# uMultimeter_ExpDev_Sch.net
KiCad netlist of a schematic drawn in Altium Designer
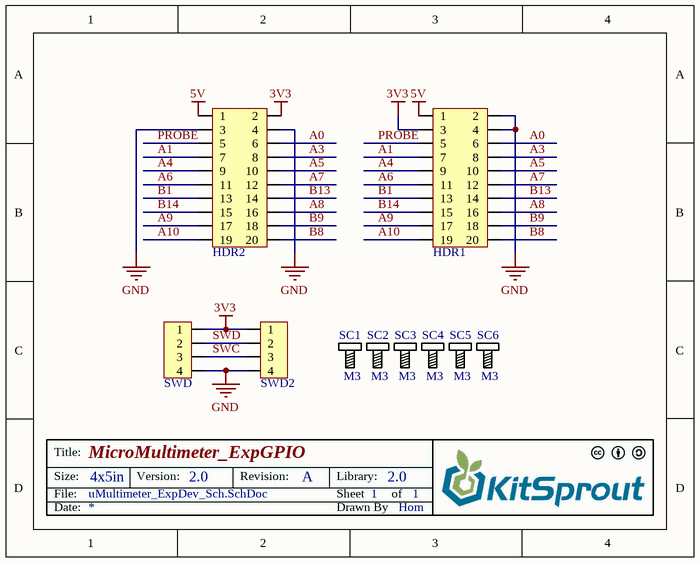
[diagram p0: uMultimeter_ExpDev_Sch.SchDoc]

(export (version "E")
  (design (tool "Eeschema 10.0.6"))
  (components
    (comp (ref "HDR1")
      (value "HDR2x10_2.54")
      (footprint "PCB_ConnectorHDR:HDR2X10_2.54_90")
      (description "Header")
      (libsource (lib "SCH_ConnectorHDR") (part "HDR2x10_2.54"))
    )
    (comp (ref "HDR2")
      (value "HDR2x10_2.54")
      (footprint "PCB_ConnectorHDR:HDR2X10_2.54_180")
      (description "Header")
      (libsource (lib "SCH_ConnectorHDR") (part "HDR2x10_2.54"))
    )
    (comp (ref "SC1")
      (value "M3")
      (footprint "PCB_Mechanical:SCRREW_M3")
      (description "Screw")
      (libsource (lib "SCH_Mechanical") (part "Screw_M3"))
    )
    (comp (ref "SC2")
      (value "M3")
      (footprint "PCB_Mechanical:SCRREW_M3")
      (description "Screw")
      (libsource (lib "SCH_Mechanical") (part "Screw_M3"))
    )
    (comp (ref "SC3")
      (value "M3")
      (footprint "PCB_Mechanical:SCRREW_M3")
      (description "Screw")
      (libsource (lib "SCH_Mechanical") (part "Screw_M3"))
    )
    (comp (ref "SC4")
      (value "M3")
      (footprint "PCB_Mechanical:SCRREW_M3")
      (description "Screw")
      (libsource (lib "SCH_Mechanical") (part "Screw_M3"))
    )
    (comp (ref "SC5")
      (value "M3")
      (footprint "PCB_Mechanical:SCRREW_M3")
      (description "Screw")
      (libsource (lib "SCH_Mechanical") (part "Screw_M3"))
    )
    (comp (ref "SC6")
      (value "M3")
      (footprint "PCB_Mechanical:SCRREW_M3")
      (description "Screw")
      (libsource (lib "SCH_Mechanical") (part "Screw_M3"))
    )
    (comp (ref "SWD")
      (value "HDR1x4_1.27T")
      (footprint "PCB_ConnectorHDR:HDR1X4_1.27_180")
      (description "Header")
      (libsource (lib "SCH_ConnectorHDR") (part "HDR1x4_1.27T"))
    )
    (comp (ref "SWD2")
      (value "HDR1x4_2.54")
      (footprint "PCB_ConnectorHDR:HDR1X4_2.54_90F")
      (description "Header")
      (libsource (lib "SCH_ConnectorHDR") (part "HDR1x4_2.54"))
    )
  )
  (nets
    (net (code "1") (name "/A0") (class "Default")
      (node (ref "HDR1") (pin "6") (pinfunction "6_6") (pintype "passive"))
      (node (ref "HDR2") (pin "6") (pinfunction "6_6") (pintype "passive"))
    )
    (net (code "2") (name "/A1") (class "Default")
      (node (ref "HDR1") (pin "7") (pinfunction "7_7") (pintype "passive"))
      (node (ref "HDR2") (pin "7") (pinfunction "7_7") (pintype "passive"))
    )
    (net (code "3") (name "/A3") (class "Default")
      (node (ref "HDR1") (pin "8") (pinfunction "8_8") (pintype "passive"))
      (node (ref "HDR2") (pin "8") (pinfunction "8_8") (pintype "passive"))
    )
    (net (code "4") (name "/A4") (class "Default")
      (node (ref "HDR1") (pin "9") (pinfunction "9_9") (pintype "passive"))
      (node (ref "HDR2") (pin "9") (pinfunction "9_9") (pintype "passive"))
    )
    (net (code "5") (name "/A5") (class "Default")
      (node (ref "HDR1") (pin "10") (pinfunction "10_10") (pintype "passive"))
      (node (ref "HDR2") (pin "10") (pinfunction "10_10") (pintype "passive"))
    )
    (net (code "6") (name "/A6") (class "Default")
      (node (ref "HDR1") (pin "11") (pinfunction "11_11") (pintype "passive"))
      (node (ref "HDR2") (pin "11") (pinfunction "11_11") (pintype "passive"))
    )
    (net (code "7") (name "/A7") (class "Default")
      (node (ref "HDR1") (pin "12") (pinfunction "12_12") (pintype "passive"))
      (node (ref "HDR2") (pin "12") (pinfunction "12_12") (pintype "passive"))
    )
    (net (code "8") (name "/A8") (class "Default")
      (node (ref "HDR1") (pin "16") (pinfunction "16_16") (pintype "passive"))
      (node (ref "HDR2") (pin "16") (pinfunction "16_16") (pintype "passive"))
    )
    (net (code "9") (name "/A9") (class "Default")
      (node (ref "HDR1") (pin "17") (pinfunction "17_17") (pintype "passive"))
      (node (ref "HDR2") (pin "17") (pinfunction "17_17") (pintype "passive"))
    )
    (net (code "10") (name "/A10") (class "Default")
      (node (ref "HDR1") (pin "19") (pinfunction "19_19") (pintype "passive"))
      (node (ref "HDR2") (pin "19") (pinfunction "19_19") (pintype "passive"))
    )
    (net (code "11") (name "/B1") (class "Default")
      (node (ref "HDR1") (pin "13") (pinfunction "13_13") (pintype "passive"))
      (node (ref "HDR2") (pin "13") (pinfunction "13_13") (pintype "passive"))
    )
    (net (code "12") (name "/B8") (class "Default")
      (node (ref "HDR1") (pin "20") (pinfunction "20_20") (pintype "passive"))
      (node (ref "HDR2") (pin "20") (pinfunction "20_20") (pintype "passive"))
    )
    (net (code "13") (name "/B9") (class "Default")
      (node (ref "HDR1") (pin "18") (pinfunction "18_18") (pintype "passive"))
      (node (ref "HDR2") (pin "18") (pinfunction "18_18") (pintype "passive"))
    )
    (net (code "14") (name "/B13") (class "Default")
      (node (ref "HDR1") (pin "14") (pinfunction "14_14") (pintype "passive"))
      (node (ref "HDR2") (pin "14") (pinfunction "14_14") (pintype "passive"))
    )
    (net (code "15") (name "/B14") (class "Default")
      (node (ref "HDR1") (pin "15") (pinfunction "15_15") (pintype "passive"))
      (node (ref "HDR2") (pin "15") (pinfunction "15_15") (pintype "passive"))
    )
    (net (code "16") (name "/PROBE") (class "Default")
      (node (ref "HDR1") (pin "5") (pinfunction "5_5") (pintype "passive"))
      (node (ref "HDR2") (pin "5") (pinfunction "5_5") (pintype "passive"))
    )
    (net (code "17") (name "/SWC") (class "Default")
      (node (ref "SWD") (pin "3") (pinfunction "3_3") (pintype "passive"))
      (node (ref "SWD2") (pin "3") (pinfunction "3_3") (pintype "passive"))
    )
    (net (code "18") (name "/SWD") (class "Default")
      (node (ref "SWD") (pin "2") (pinfunction "2_2") (pintype "passive"))
      (node (ref "SWD2") (pin "2") (pinfunction "2_2") (pintype "passive"))
    )
    (net (code "19") (name "3V3") (class "Default")
      (node (ref "HDR1") (pin "3") (pinfunction "3_3") (pintype "passive"))
      (node (ref "HDR2") (pin "2") (pinfunction "2_2") (pintype "passive"))
      (node (ref "SWD") (pin "1") (pinfunction "1_1") (pintype "passive"))
      (node (ref "SWD2") (pin "1") (pinfunction "1_1") (pintype "passive"))
    )
    (net (code "20") (name "5V") (class "Default")
      (node (ref "HDR1") (pin "1") (pinfunction "1_1") (pintype "passive"))
      (node (ref "HDR2") (pin "1") (pinfunction "1_1") (pintype "passive"))
    )
    (net (code "21") (name "GND") (class "Default")
      (node (ref "HDR1") (pin "2") (pinfunction "2_2") (pintype "passive"))
      (node (ref "HDR1") (pin "4") (pinfunction "4_4") (pintype "passive"))
      (node (ref "HDR2") (pin "3") (pinfunction "3_3") (pintype "passive"))
      (node (ref "HDR2") (pin "4") (pinfunction "4_4") (pintype "passive"))
      (node (ref "SWD") (pin "4") (pinfunction "4_4") (pintype "passive"))
      (node (ref "SWD2") (pin "4") (pinfunction "4_4") (pintype "passive"))
    )
  )
)
